# Rangakaian_OP-AMP_Theo.net
KiCad netlist of a schematic drawn in EAGLE
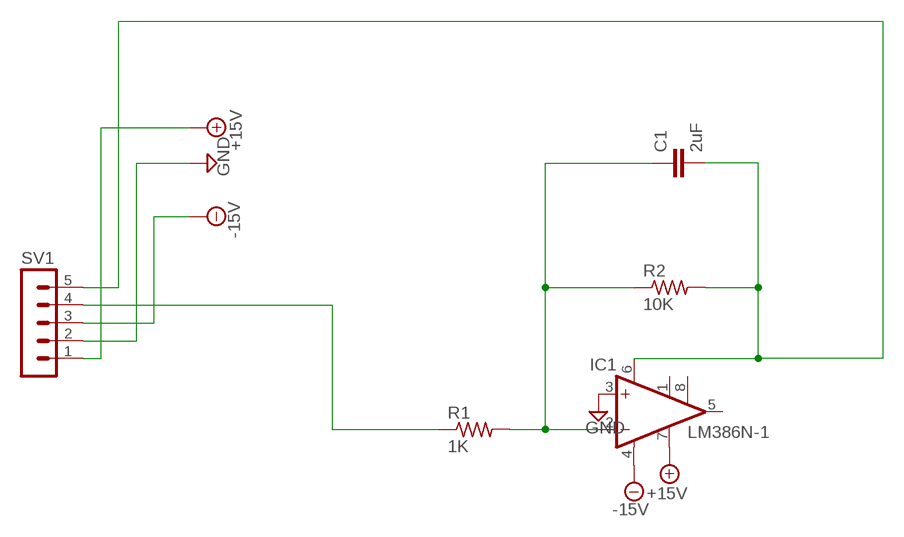
[diagram p0: schematic, sheet 1]

(export (version "E")
  (design (tool "Eeschema 10.0.6"))
  (components
    (comp (ref "C1")
      (value "2uF")
      (footprint "eagle-import:C025-024X044")
      (libsource (lib "eagle-import") (part "C-EU025-024X044"))
    )
    (comp (ref "IC1")
      (value "LM386N-1")
      (footprint "eagle-import:DIL08")
      (libsource (lib "eagle-import") (part "LM386?-N1"))
    )
    (comp (ref "R1")
      (value "1K")
      (footprint "eagle-import:0204_5")
      (libsource (lib "eagle-import") (part "R-US_0204/5"))
    )
    (comp (ref "R2")
      (value "10K")
      (footprint "eagle-import:0204_5")
      (libsource (lib "eagle-import") (part "R-US_0204/5"))
    )
    (comp (ref "SV1")
      (value "MA05-1")
      (footprint "eagle-import:MA05-1")
      (libsource (lib "eagle-import") (part "MA05-1"))
    )
  )
  (nets
    (net (code "1") (name "+15V") (class "Default")
      (node (ref "IC1") (pin "7") (pinfunction "BYPASS_7") (pintype "passive"))
      (node (ref "SV1") (pin "1") (pinfunction "1_1") (pintype "passive"))
    )
    (net (code "2") (name "-15V") (class "Default")
      (node (ref "IC1") (pin "4") (pinfunction "GND_4") (pintype "power_in"))
      (node (ref "SV1") (pin "3") (pinfunction "3_3") (pintype "passive"))
    )
    (net (code "3") (name "GND") (class "Default")
      (node (ref "IC1") (pin "3") (pinfunction "+IN_3") (pintype "input"))
      (node (ref "SV1") (pin "2") (pinfunction "2_2") (pintype "passive"))
    )
    (net (code "4") (name "Net-(IC1--IN)") (class "Default")
      (node (ref "C1") (pin "1") (pinfunction "1_1") (pintype "passive"))
      (node (ref "IC1") (pin "2") (pinfunction "-IN_2") (pintype "input"))
      (node (ref "R1") (pin "2") (pinfunction "2_2") (pintype "passive"))
      (node (ref "R2") (pin "1") (pinfunction "1_1") (pintype "passive"))
    )
    (net (code "5") (name "Net-(IC1-VS)") (class "Default")
      (node (ref "C1") (pin "2") (pinfunction "2_2") (pintype "passive"))
      (node (ref "IC1") (pin "6") (pinfunction "VS_6") (pintype "power_in"))
      (node (ref "R2") (pin "2") (pinfunction "2_2") (pintype "passive"))
      (node (ref "SV1") (pin "5") (pinfunction "5_5") (pintype "passive"))
    )
    (net (code "6") (name "Net-(R1-Pad1)") (class "Default")
      (node (ref "R1") (pin "1") (pinfunction "1_1") (pintype "passive"))
      (node (ref "SV1") (pin "4") (pinfunction "4_4") (pintype "passive"))
    )
    (net (code "7") (name "unconnected-(IC1-GAIN-Pad1)") (class "Default")
      (node (ref "IC1") (pin "1") (pinfunction "GAIN_1") (pintype "passive"))
    )
    (net (code "8") (name "unconnected-(IC1-GAIN-Pad8)") (class "Default")
      (node (ref "IC1") (pin "8") (pinfunction "GAIN_8") (pintype "passive"))
    )
    (net (code "9") (name "unconnected-(IC1-OUT-Pad5)") (class "Default")
      (node (ref "IC1") (pin "5") (pinfunction "OUT_5") (pintype "output"))
    )
  )
)
